# Shuttle.net
KiCad netlist of a schematic drawn in EAGLE
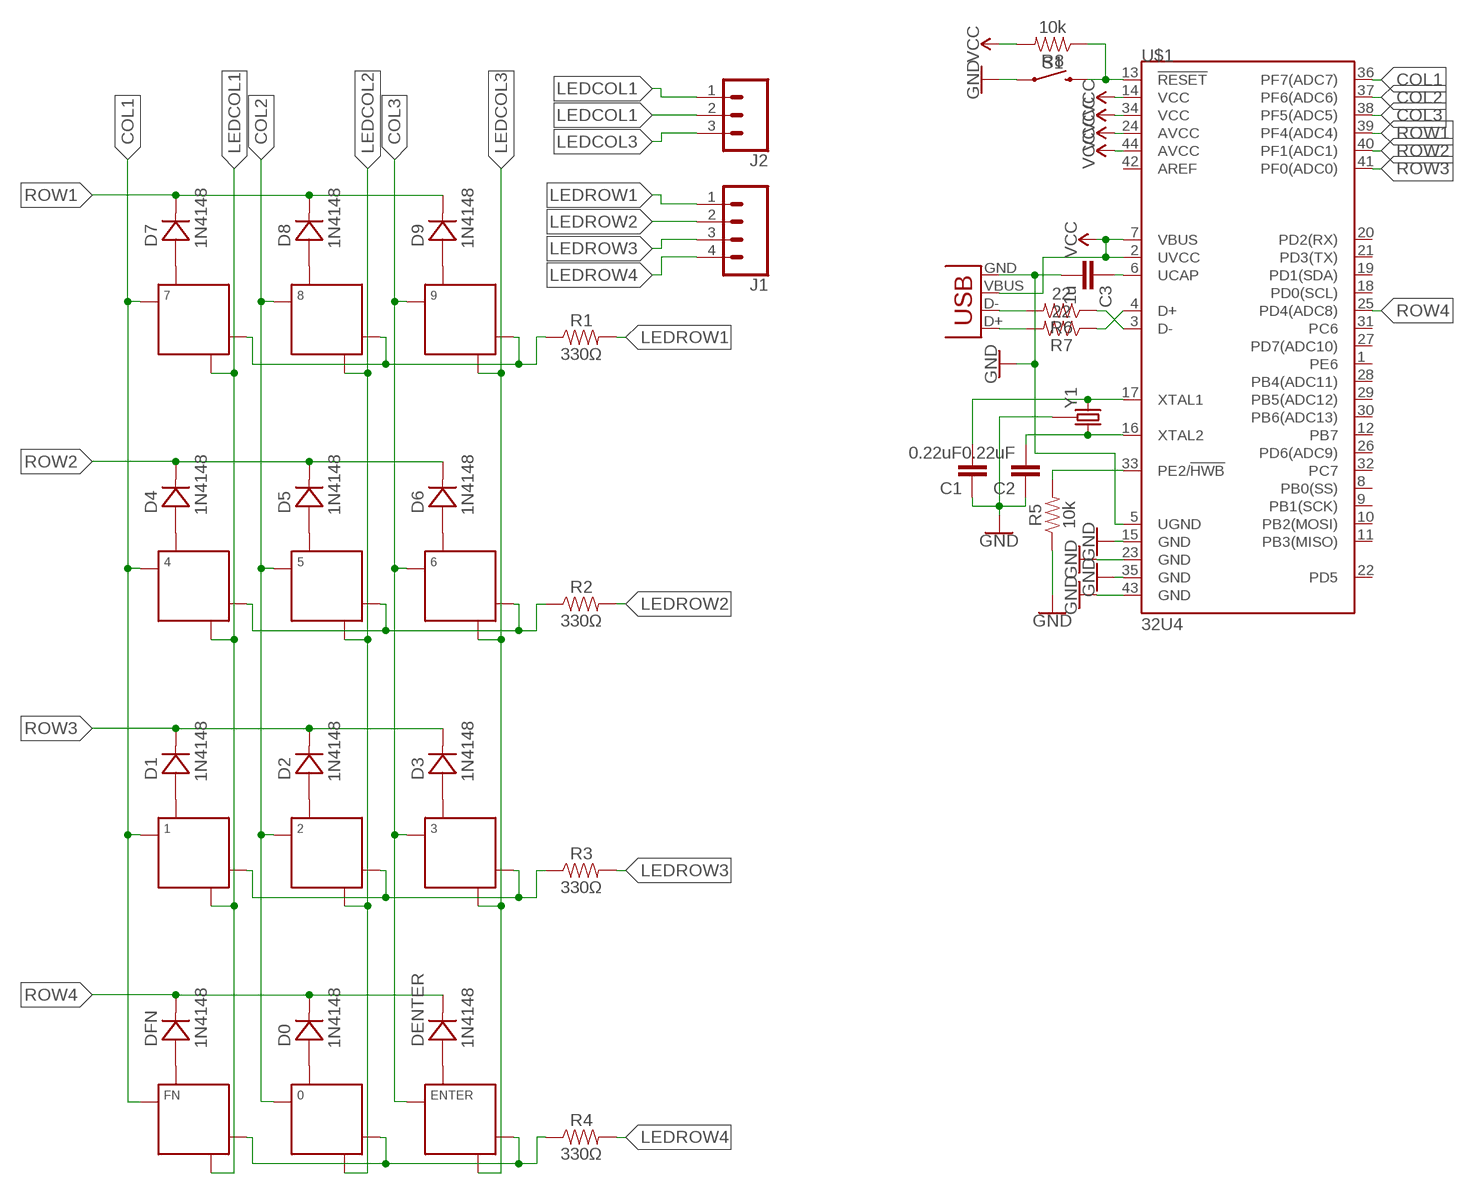
[diagram p0: schematic, sheet 1]

(export (version "E")
  (design (tool "Eeschema 10.0.6"))
  (components
    (comp (ref "0")
      (value "KEYSWITCH-LED-ALPSMX-1U-LED")
      (footprint "eagle-import:ALPSMX-1U-LED")
      (libsource (lib "eagle-import") (part "KEYSWITCH-LED-ALPSMX-1U-LED"))
    )
    (comp (ref "1")
      (value "KEYSWITCH-LED-ALPSMX-1U-LED")
      (footprint "eagle-import:ALPSMX-1U-LED")
      (libsource (lib "eagle-import") (part "KEYSWITCH-LED-ALPSMX-1U-LED"))
    )
    (comp (ref "2")
      (value "KEYSWITCH-LED-ALPSMX-1U-LED")
      (footprint "eagle-import:ALPSMX-1U-LED")
      (libsource (lib "eagle-import") (part "KEYSWITCH-LED-ALPSMX-1U-LED"))
    )
    (comp (ref "3")
      (value "KEYSWITCH-LED-ALPSMX-1U-LED")
      (footprint "eagle-import:ALPSMX-1U-LED")
      (libsource (lib "eagle-import") (part "KEYSWITCH-LED-ALPSMX-1U-LED"))
    )
    (comp (ref "4")
      (value "KEYSWITCH-LED-ALPSMX-1U-LED")
      (footprint "eagle-import:ALPSMX-1U-LED")
      (libsource (lib "eagle-import") (part "KEYSWITCH-LED-ALPSMX-1U-LED"))
    )
    (comp (ref "5")
      (value "KEYSWITCH-LED-ALPSMX-1U-LED")
      (footprint "eagle-import:ALPSMX-1U-LED")
      (libsource (lib "eagle-import") (part "KEYSWITCH-LED-ALPSMX-1U-LED"))
    )
    (comp (ref "6")
      (value "KEYSWITCH-LED-ALPSMX-1U-LED")
      (footprint "eagle-import:ALPSMX-1U-LED")
      (libsource (lib "eagle-import") (part "KEYSWITCH-LED-ALPSMX-1U-LED"))
    )
    (comp (ref "7")
      (value "KEYSWITCH-LED-ALPSMX-1U-LED")
      (footprint "eagle-import:ALPSMX-1U-LED")
      (libsource (lib "eagle-import") (part "KEYSWITCH-LED-ALPSMX-1U-LED"))
    )
    (comp (ref "8")
      (value "KEYSWITCH-LED-ALPSMX-1U-LED")
      (footprint "eagle-import:ALPSMX-1U-LED")
      (libsource (lib "eagle-import") (part "KEYSWITCH-LED-ALPSMX-1U-LED"))
    )
    (comp (ref "9")
      (value "KEYSWITCH-LED-ALPSMX-1U-LED")
      (footprint "eagle-import:ALPSMX-1U-LED")
      (libsource (lib "eagle-import") (part "KEYSWITCH-LED-ALPSMX-1U-LED"))
    )
    (comp (ref "C1")
      (value "0.22uF")
      (footprint "eagle-import:0603")
      (libsource (lib "eagle-import") (part "0.22UF-0603-25V-10%"))
    )
    (comp (ref "C2")
      (value "0.22uF")
      (footprint "eagle-import:0603")
      (libsource (lib "eagle-import") (part "0.22UF-0603-25V-10%"))
    )
    (comp (ref "C3")
      (value "1u")
      (footprint "eagle-import:0603")
      (libsource (lib "eagle-import") (part "0.22UF-0603-25V-10%"))
    )
    (comp (ref "D0")
      (value "1N4148")
      (footprint "eagle-import:DO-35")
      (libsource (lib "eagle-import") (part "DIODE-DO-35"))
    )
    (comp (ref "D1")
      (value "1N4148")
      (footprint "eagle-import:DO-35")
      (libsource (lib "eagle-import") (part "DIODE-DO-35"))
    )
    (comp (ref "D2")
      (value "1N4148")
      (footprint "eagle-import:DO-35")
      (libsource (lib "eagle-import") (part "DIODE-DO-35"))
    )
    (comp (ref "D3")
      (value "1N4148")
      (footprint "eagle-import:DO-35")
      (libsource (lib "eagle-import") (part "DIODE-DO-35"))
    )
    (comp (ref "D4")
      (value "1N4148")
      (footprint "eagle-import:DO-35")
      (libsource (lib "eagle-import") (part "DIODE-DO-35"))
    )
    (comp (ref "D5")
      (value "1N4148")
      (footprint "eagle-import:DO-35")
      (libsource (lib "eagle-import") (part "DIODE-DO-35"))
    )
    (comp (ref "D6")
      (value "1N4148")
      (footprint "eagle-import:DO-35")
      (libsource (lib "eagle-import") (part "DIODE-DO-35"))
    )
    (comp (ref "D7")
      (value "1N4148")
      (footprint "eagle-import:DO-35")
      (libsource (lib "eagle-import") (part "DIODE-DO-35"))
    )
    (comp (ref "D8")
      (value "1N4148")
      (footprint "eagle-import:DO-35")
      (libsource (lib "eagle-import") (part "DIODE-DO-35"))
    )
    (comp (ref "D9")
      (value "1N4148")
      (footprint "eagle-import:DO-35")
      (libsource (lib "eagle-import") (part "DIODE-DO-35"))
    )
    (comp (ref "DENTER")
      (value "1N4148")
      (footprint "eagle-import:DO-35")
      (libsource (lib "eagle-import") (part "DIODE-DO-35"))
    )
    (comp (ref "DFN")
      (value "1N4148")
      (footprint "eagle-import:DO-35")
      (libsource (lib "eagle-import") (part "DIODE-DO-35"))
    )
    (comp (ref "ENTER")
      (value "KEYSWITCH-LED-ALPSMX-1U-LED")
      (footprint "eagle-import:ALPSMX-1U-LED")
      (libsource (lib "eagle-import") (part "KEYSWITCH-LED-ALPSMX-1U-LED"))
    )
    (comp (ref "FN")
      (value "KEYSWITCH-LED-ALPSMX-1U-LED")
      (footprint "eagle-import:ALPSMX-1U-LED")
      (libsource (lib "eagle-import") (part "KEYSWITCH-LED-ALPSMX-1U-LED"))
    )
    (comp (ref "J1")
      (value "CONN_04")
      (footprint "eagle-import:1X04")
      (libsource (lib "eagle-import") (part "CONN_04"))
    )
    (comp (ref "J2")
      (value "CONN_03")
      (footprint "eagle-import:1X03")
      (libsource (lib "eagle-import") (part "CONN_03"))
    )
    (comp (ref "R1")
      (value "330Ω")
      (footprint "eagle-import:AXIAL-0.3")
      (libsource (lib "eagle-import") (part "RESISTORAXIAL-0.3"))
    )
    (comp (ref "R2")
      (value "330Ω")
      (footprint "eagle-import:AXIAL-0.3")
      (libsource (lib "eagle-import") (part "RESISTORAXIAL-0.3"))
    )
    (comp (ref "R3")
      (value "330Ω")
      (footprint "eagle-import:AXIAL-0.3")
      (libsource (lib "eagle-import") (part "RESISTORAXIAL-0.3"))
    )
    (comp (ref "R4")
      (value "330Ω")
      (footprint "eagle-import:AXIAL-0.3")
      (libsource (lib "eagle-import") (part "RESISTORAXIAL-0.3"))
    )
    (comp (ref "R5")
      (value "10k")
      (footprint "eagle-import:AXIAL-0.3")
      (libsource (lib "eagle-import") (part "RESISTORAXIAL-0.3"))
    )
    (comp (ref "R6")
      (value "22")
      (footprint "eagle-import:AXIAL-0.3")
      (libsource (lib "eagle-import") (part "RESISTORAXIAL-0.3"))
    )
    (comp (ref "R7")
      (value "22")
      (footprint "eagle-import:AXIAL-0.3")
      (libsource (lib "eagle-import") (part "RESISTORAXIAL-0.3"))
    )
    (comp (ref "R8")
      (value "10k")
      (footprint "eagle-import:AXIAL-0.3")
      (libsource (lib "eagle-import") (part "RESISTORAXIAL-0.3"))
    )
    (comp (ref "S1")
      (value "MOMENTARY-SWITCH-SPST-PTH-6.0MM")
      (footprint "eagle-import:TACTILE_SWITCH_PTH_6.0MM")
      (libsource (lib "eagle-import") (part "MOMENTARY-SWITCH-SPST-PTH-6.0MM"))
    )
    (comp (ref "U$1")
      (value "32U4")
      (footprint "eagle-import:TQFP44")
      (libsource (lib "eagle-import") (part "ATMEGA32U4TQFP-44"))
    )
    (comp (ref "X1")
      (value "USB-MB-H")
      (footprint "eagle-import:USB-MB-H")
      (libsource (lib "eagle-import") (part "USB-MB-H"))
    )
    (comp (ref "Y1")
      (value "CRYSTAL-GROUNDEDSMD-5X3.2")
      (footprint "eagle-import:CRYSTAL-SMD-5X3.2-4PAD")
      (libsource (lib "eagle-import") (part "CRYSTAL-GROUNDEDSMD-5X3.2"))
    )
  )
  (nets
    (net (code "1") (name "COL1") (class "Default")
      (node (ref "1") (pin "ALPS1") (pinfunction "P0_ALPS1") (pintype "bidirectional"))
      (node (ref "1") (pin "MX1") (pinfunction "P0_MX1") (pintype "bidirectional"))
      (node (ref "4") (pin "ALPS1") (pinfunction "P0_ALPS1") (pintype "bidirectional"))
      (node (ref "4") (pin "MX1") (pinfunction "P0_MX1") (pintype "bidirectional"))
      (node (ref "7") (pin "ALPS1") (pinfunction "P0_ALPS1") (pintype "bidirectional"))
      (node (ref "7") (pin "MX1") (pinfunction "P0_MX1") (pintype "bidirectional"))
      (node (ref "FN") (pin "ALPS1") (pinfunction "P0_ALPS1") (pintype "bidirectional"))
      (node (ref "FN") (pin "MX1") (pinfunction "P0_MX1") (pintype "bidirectional"))
      (node (ref "U$1") (pin "36") (pinfunction "PF7(ADC7)_36") (pintype "bidirectional"))
    )
    (net (code "2") (name "COL2") (class "Default")
      (node (ref "0") (pin "ALPS1") (pinfunction "P0_ALPS1") (pintype "bidirectional"))
      (node (ref "0") (pin "MX1") (pinfunction "P0_MX1") (pintype "bidirectional"))
      (node (ref "2") (pin "ALPS1") (pinfunction "P0_ALPS1") (pintype "bidirectional"))
      (node (ref "2") (pin "MX1") (pinfunction "P0_MX1") (pintype "bidirectional"))
      (node (ref "5") (pin "ALPS1") (pinfunction "P0_ALPS1") (pintype "bidirectional"))
      (node (ref "5") (pin "MX1") (pinfunction "P0_MX1") (pintype "bidirectional"))
      (node (ref "8") (pin "ALPS1") (pinfunction "P0_ALPS1") (pintype "bidirectional"))
      (node (ref "8") (pin "MX1") (pinfunction "P0_MX1") (pintype "bidirectional"))
      (node (ref "U$1") (pin "37") (pinfunction "PF6(ADC6)_37") (pintype "bidirectional"))
    )
    (net (code "3") (name "COL3") (class "Default")
      (node (ref "3") (pin "ALPS1") (pinfunction "P0_ALPS1") (pintype "bidirectional"))
      (node (ref "3") (pin "MX1") (pinfunction "P0_MX1") (pintype "bidirectional"))
      (node (ref "6") (pin "ALPS1") (pinfunction "P0_ALPS1") (pintype "bidirectional"))
      (node (ref "6") (pin "MX1") (pinfunction "P0_MX1") (pintype "bidirectional"))
      (node (ref "9") (pin "ALPS1") (pinfunction "P0_ALPS1") (pintype "bidirectional"))
      (node (ref "9") (pin "MX1") (pinfunction "P0_MX1") (pintype "bidirectional"))
      (node (ref "ENTER") (pin "ALPS1") (pinfunction "P0_ALPS1") (pintype "bidirectional"))
      (node (ref "ENTER") (pin "MX1") (pinfunction "P0_MX1") (pintype "bidirectional"))
      (node (ref "U$1") (pin "38") (pinfunction "PF5(ADC5)_38") (pintype "bidirectional"))
    )
    (net (code "4") (name "GND") (class "Default")
      (node (ref "C1") (pin "1") (pinfunction "1_1") (pintype "passive"))
      (node (ref "C2") (pin "1") (pinfunction "1_1") (pintype "passive"))
      (node (ref "C3") (pin "2") (pinfunction "2_2") (pintype "passive"))
      (node (ref "R5") (pin "P$1") (pinfunction "1_P$1") (pintype "passive"))
      (node (ref "S1") (pin "1") (pinfunction "1_1") (pintype "passive"))
      (node (ref "U$1") (pin "15") (pinfunction "GND_15") (pintype "bidirectional"))
      (node (ref "U$1") (pin "23") (pinfunction "GND_23") (pintype "bidirectional"))
      (node (ref "U$1") (pin "35") (pinfunction "GND_35") (pintype "bidirectional"))
      (node (ref "U$1") (pin "43") (pinfunction "GND_43") (pintype "bidirectional"))
      (node (ref "U$1") (pin "5") (pinfunction "UGND_5") (pintype "bidirectional"))
      (node (ref "X1") (pin "GND") (pinfunction "GND_GND") (pintype "bidirectional"))
      (node (ref "Y1") (pin "2") (pinfunction "3_2") (pintype "passive"))
      (node (ref "Y1") (pin "4") (pinfunction "3_4") (pintype "passive"))
    )
    (net (code "5") (name "LEDCOL1") (class "Default")
      (node (ref "1") (pin "LED+") (pinfunction "LED+_LED+") (pintype "bidirectional"))
      (node (ref "4") (pin "LED+") (pinfunction "LED+_LED+") (pintype "bidirectional"))
      (node (ref "7") (pin "LED+") (pinfunction "LED+_LED+") (pintype "bidirectional"))
      (node (ref "FN") (pin "LED+") (pinfunction "LED+_LED+") (pintype "bidirectional"))
      (node (ref "J2") (pin "1") (pinfunction "1_1") (pintype "passive"))
      (node (ref "J2") (pin "2") (pinfunction "2_2") (pintype "passive"))
    )
    (net (code "6") (name "LEDCOL2") (class "Default")
      (node (ref "0") (pin "LED+") (pinfunction "LED+_LED+") (pintype "bidirectional"))
      (node (ref "2") (pin "LED+") (pinfunction "LED+_LED+") (pintype "bidirectional"))
      (node (ref "5") (pin "LED+") (pinfunction "LED+_LED+") (pintype "bidirectional"))
      (node (ref "8") (pin "LED+") (pinfunction "LED+_LED+") (pintype "bidirectional"))
    )
    (net (code "7") (name "LEDCOL3") (class "Default")
      (node (ref "3") (pin "LED+") (pinfunction "LED+_LED+") (pintype "bidirectional"))
      (node (ref "6") (pin "LED+") (pinfunction "LED+_LED+") (pintype "bidirectional"))
      (node (ref "9") (pin "LED+") (pinfunction "LED+_LED+") (pintype "bidirectional"))
      (node (ref "ENTER") (pin "LED+") (pinfunction "LED+_LED+") (pintype "bidirectional"))
      (node (ref "J2") (pin "3") (pinfunction "3_3") (pintype "passive"))
    )
    (net (code "8") (name "LEDROW1") (class "Default")
      (node (ref "J1") (pin "1") (pinfunction "1_1") (pintype "passive"))
      (node (ref "R1") (pin "P$2") (pinfunction "2_P$2") (pintype "passive"))
    )
    (net (code "9") (name "LEDROW2") (class "Default")
      (node (ref "J1") (pin "2") (pinfunction "2_2") (pintype "passive"))
      (node (ref "R2") (pin "P$2") (pinfunction "2_P$2") (pintype "passive"))
    )
    (net (code "10") (name "LEDROW3") (class "Default")
      (node (ref "J1") (pin "3") (pinfunction "3_3") (pintype "passive"))
      (node (ref "R3") (pin "P$2") (pinfunction "2_P$2") (pintype "passive"))
    )
    (net (code "11") (name "LEDROW4") (class "Default")
      (node (ref "J1") (pin "4") (pinfunction "4_4") (pintype "passive"))
      (node (ref "R4") (pin "P$2") (pinfunction "2_P$2") (pintype "passive"))
    )
    (net (code "12") (name "Net-(0-P1-PadALPS2)") (class "Default")
      (node (ref "0") (pin "ALPS2") (pinfunction "P1_ALPS2") (pintype "bidirectional"))
      (node (ref "0") (pin "MX2") (pinfunction "P1_MX2") (pintype "bidirectional"))
      (node (ref "D0") (pin "A") (pinfunction "A_A") (pintype "passive"))
    )
    (net (code "13") (name "Net-(1-P1-PadALPS2)") (class "Default")
      (node (ref "1") (pin "ALPS2") (pinfunction "P1_ALPS2") (pintype "bidirectional"))
      (node (ref "1") (pin "MX2") (pinfunction "P1_MX2") (pintype "bidirectional"))
      (node (ref "D1") (pin "A") (pinfunction "A_A") (pintype "passive"))
    )
    (net (code "14") (name "Net-(2-P1-PadALPS2)") (class "Default")
      (node (ref "2") (pin "ALPS2") (pinfunction "P1_ALPS2") (pintype "bidirectional"))
      (node (ref "2") (pin "MX2") (pinfunction "P1_MX2") (pintype "bidirectional"))
      (node (ref "D2") (pin "A") (pinfunction "A_A") (pintype "passive"))
    )
    (net (code "15") (name "Net-(3-P1-PadALPS2)") (class "Default")
      (node (ref "3") (pin "ALPS2") (pinfunction "P1_ALPS2") (pintype "bidirectional"))
      (node (ref "3") (pin "MX2") (pinfunction "P1_MX2") (pintype "bidirectional"))
      (node (ref "D3") (pin "A") (pinfunction "A_A") (pintype "passive"))
    )
    (net (code "16") (name "Net-(4-P1-PadALPS2)") (class "Default")
      (node (ref "4") (pin "ALPS2") (pinfunction "P1_ALPS2") (pintype "bidirectional"))
      (node (ref "4") (pin "MX2") (pinfunction "P1_MX2") (pintype "bidirectional"))
      (node (ref "D4") (pin "A") (pinfunction "A_A") (pintype "passive"))
    )
    (net (code "17") (name "Net-(5-P1-PadALPS2)") (class "Default")
      (node (ref "5") (pin "ALPS2") (pinfunction "P1_ALPS2") (pintype "bidirectional"))
      (node (ref "5") (pin "MX2") (pinfunction "P1_MX2") (pintype "bidirectional"))
      (node (ref "D5") (pin "A") (pinfunction "A_A") (pintype "passive"))
    )
    (net (code "18") (name "Net-(6-P1-PadALPS2)") (class "Default")
      (node (ref "6") (pin "ALPS2") (pinfunction "P1_ALPS2") (pintype "bidirectional"))
      (node (ref "6") (pin "MX2") (pinfunction "P1_MX2") (pintype "bidirectional"))
      (node (ref "D6") (pin "A") (pinfunction "A_A") (pintype "passive"))
    )
    (net (code "19") (name "Net-(7-P1-PadALPS2)") (class "Default")
      (node (ref "7") (pin "ALPS2") (pinfunction "P1_ALPS2") (pintype "bidirectional"))
      (node (ref "7") (pin "MX2") (pinfunction "P1_MX2") (pintype "bidirectional"))
      (node (ref "D7") (pin "A") (pinfunction "A_A") (pintype "passive"))
    )
    (net (code "20") (name "Net-(8-P1-PadALPS2)") (class "Default")
      (node (ref "8") (pin "ALPS2") (pinfunction "P1_ALPS2") (pintype "bidirectional"))
      (node (ref "8") (pin "MX2") (pinfunction "P1_MX2") (pintype "bidirectional"))
      (node (ref "D8") (pin "A") (pinfunction "A_A") (pintype "passive"))
    )
    (net (code "21") (name "Net-(9-P1-PadALPS2)") (class "Default")
      (node (ref "9") (pin "ALPS2") (pinfunction "P1_ALPS2") (pintype "bidirectional"))
      (node (ref "9") (pin "MX2") (pinfunction "P1_MX2") (pintype "bidirectional"))
      (node (ref "D9") (pin "A") (pinfunction "A_A") (pintype "passive"))
    )
    (net (code "22") (name "Net-(DENTER-PadA)") (class "Default")
      (node (ref "DENTER") (pin "A") (pinfunction "A_A") (pintype "passive"))
      (node (ref "ENTER") (pin "ALPS2") (pinfunction "P1_ALPS2") (pintype "bidirectional"))
      (node (ref "ENTER") (pin "MX2") (pinfunction "P1_MX2") (pintype "bidirectional"))
    )
    (net (code "23") (name "Net-(DFN-PadA)") (class "Default")
      (node (ref "DFN") (pin "A") (pinfunction "A_A") (pintype "passive"))
      (node (ref "FN") (pin "ALPS2") (pinfunction "P1_ALPS2") (pintype "bidirectional"))
      (node (ref "FN") (pin "MX2") (pinfunction "P1_MX2") (pintype "bidirectional"))
    )
    (net (code "24") (name "Net-(R1-1)") (class "Default")
      (node (ref "7") (pin "LED-") (pinfunction "LED-_LED-") (pintype "bidirectional"))
      (node (ref "8") (pin "LED-") (pinfunction "LED-_LED-") (pintype "bidirectional"))
      (node (ref "9") (pin "LED-") (pinfunction "LED-_LED-") (pintype "bidirectional"))
      (node (ref "R1") (pin "P$1") (pinfunction "1_P$1") (pintype "passive"))
    )
    (net (code "25") (name "Net-(R2-1)") (class "Default")
      (node (ref "4") (pin "LED-") (pinfunction "LED-_LED-") (pintype "bidirectional"))
      (node (ref "5") (pin "LED-") (pinfunction "LED-_LED-") (pintype "bidirectional"))
      (node (ref "6") (pin "LED-") (pinfunction "LED-_LED-") (pintype "bidirectional"))
      (node (ref "R2") (pin "P$1") (pinfunction "1_P$1") (pintype "passive"))
    )
    (net (code "26") (name "Net-(R3-1)") (class "Default")
      (node (ref "1") (pin "LED-") (pinfunction "LED-_LED-") (pintype "bidirectional"))
      (node (ref "2") (pin "LED-") (pinfunction "LED-_LED-") (pintype "bidirectional"))
      (node (ref "3") (pin "LED-") (pinfunction "LED-_LED-") (pintype "bidirectional"))
      (node (ref "R3") (pin "P$1") (pinfunction "1_P$1") (pintype "passive"))
    )
    (net (code "27") (name "Net-(R4-1)") (class "Default")
      (node (ref "0") (pin "LED-") (pinfunction "LED-_LED-") (pintype "bidirectional"))
      (node (ref "ENTER") (pin "LED-") (pinfunction "LED-_LED-") (pintype "bidirectional"))
      (node (ref "FN") (pin "LED-") (pinfunction "LED-_LED-") (pintype "bidirectional"))
      (node (ref "R4") (pin "P$1") (pinfunction "1_P$1") (pintype "passive"))
    )
    (net (code "28") (name "Net-(R5-2)") (class "Default")
      (node (ref "R5") (pin "P$2") (pinfunction "2_P$2") (pintype "passive"))
      (node (ref "U$1") (pin "33") (pinfunction "PE2/~{HWB}_33") (pintype "bidirectional"))
    )
    (net (code "29") (name "Net-(R6-1)") (class "Default")
      (node (ref "R6") (pin "P$1") (pinfunction "1_P$1") (pintype "passive"))
      (node (ref "U$1") (pin "3") (pinfunction "D-_3") (pintype "bidirectional"))
    )
    (net (code "30") (name "Net-(R6-2)") (class "Default")
      (node (ref "R6") (pin "P$2") (pinfunction "2_P$2") (pintype "passive"))
      (node (ref "X1") (pin "D-") (pinfunction "D-_D-") (pintype "bidirectional"))
    )
    (net (code "31") (name "Net-(R7-1)") (class "Default")
      (node (ref "R7") (pin "P$1") (pinfunction "1_P$1") (pintype "passive"))
      (node (ref "U$1") (pin "4") (pinfunction "D+_4") (pintype "bidirectional"))
    )
    (net (code "32") (name "Net-(R7-2)") (class "Default")
      (node (ref "R7") (pin "P$2") (pinfunction "2_P$2") (pintype "passive"))
      (node (ref "X1") (pin "D+") (pinfunction "D+_D+") (pintype "bidirectional"))
    )
    (net (code "33") (name "Net-(R8-1)") (class "Default")
      (node (ref "R8") (pin "P$1") (pinfunction "1_P$1") (pintype "passive"))
      (node (ref "S1") (pin "3") (pinfunction "2_3") (pintype "passive"))
      (node (ref "U$1") (pin "13") (pinfunction "~{RESET}_13") (pintype "bidirectional"))
    )
    (net (code "34") (name "Net-(U$1-UCAP)") (class "Default")
      (node (ref "C3") (pin "1") (pinfunction "1_1") (pintype "passive"))
      (node (ref "U$1") (pin "6") (pinfunction "UCAP_6") (pintype "bidirectional"))
    )
    (net (code "35") (name "Net-(U$1-XTAL1)") (class "Default")
      (node (ref "C1") (pin "2") (pinfunction "2_2") (pintype "passive"))
      (node (ref "U$1") (pin "17") (pinfunction "XTAL1_17") (pintype "bidirectional"))
      (node (ref "Y1") (pin "3") (pinfunction "1_3") (pintype "passive"))
    )
    (net (code "36") (name "Net-(U$1-XTAL2)") (class "Default")
      (node (ref "C2") (pin "2") (pinfunction "2_2") (pintype "passive"))
      (node (ref "U$1") (pin "16") (pinfunction "XTAL2_16") (pintype "bidirectional"))
      (node (ref "Y1") (pin "1") (pinfunction "2_1") (pintype "passive"))
    )
    (net (code "37") (name "ROW1") (class "Default")
      (node (ref "D7") (pin "C") (pinfunction "C_C") (pintype "passive"))
      (node (ref "D8") (pin "C") (pinfunction "C_C") (pintype "passive"))
      (node (ref "D9") (pin "C") (pinfunction "C_C") (pintype "passive"))
      (node (ref "U$1") (pin "39") (pinfunction "PF4(ADC4)_39") (pintype "bidirectional"))
    )
    (net (code "38") (name "ROW2") (class "Default")
      (node (ref "D4") (pin "C") (pinfunction "C_C") (pintype "passive"))
      (node (ref "D5") (pin "C") (pinfunction "C_C") (pintype "passive"))
      (node (ref "D6") (pin "C") (pinfunction "C_C") (pintype "passive"))
      (node (ref "U$1") (pin "40") (pinfunction "PF1(ADC1)_40") (pintype "bidirectional"))
    )
    (net (code "39") (name "ROW3") (class "Default")
      (node (ref "D1") (pin "C") (pinfunction "C_C") (pintype "passive"))
      (node (ref "D2") (pin "C") (pinfunction "C_C") (pintype "passive"))
      (node (ref "D3") (pin "C") (pinfunction "C_C") (pintype "passive"))
      (node (ref "U$1") (pin "41") (pinfunction "PF0(ADC0)_41") (pintype "bidirectional"))
    )
    (net (code "40") (name "ROW4") (class "Default")
      (node (ref "D0") (pin "C") (pinfunction "C_C") (pintype "passive"))
      (node (ref "DENTER") (pin "C") (pinfunction "C_C") (pintype "passive"))
      (node (ref "DFN") (pin "C") (pinfunction "C_C") (pintype "passive"))
      (node (ref "U$1") (pin "25") (pinfunction "PD4(ADC8)_25") (pintype "bidirectional"))
    )
    (net (code "41") (name "VCC") (class "Default")
      (node (ref "R8") (pin "P$2") (pinfunction "2_P$2") (pintype "passive"))
      (node (ref "U$1") (pin "14") (pinfunction "VCC_14") (pintype "bidirectional"))
      (node (ref "U$1") (pin "2") (pinfunction "UVCC_2") (pintype "bidirectional"))
      (node (ref "U$1") (pin "24") (pinfunction "AVCC_24") (pintype "bidirectional"))
      (node (ref "U$1") (pin "34") (pinfunction "VCC_34") (pintype "bidirectional"))
      (node (ref "U$1") (pin "44") (pinfunction "AVCC_44") (pintype "bidirectional"))
      (node (ref "U$1") (pin "7") (pinfunction "VBUS_7") (pintype "bidirectional"))
      (node (ref "X1") (pin "VBUS") (pinfunction "VBUS_VBUS") (pintype "bidirectional"))
    )
    (net (code "42") (name "unconnected-(U$1-AREF-Pad42)") (class "Default")
      (node (ref "U$1") (pin "42") (pinfunction "AREF_42") (pintype "bidirectional"))
    )
    (net (code "43") (name "unconnected-(U$1-PB0(SS)-Pad8)") (class "Default")
      (node (ref "U$1") (pin "8") (pinfunction "PB0(SS)_8") (pintype "bidirectional"))
    )
    (net (code "44") (name "unconnected-(U$1-PB1(SCK)-Pad9)") (class "Default")
      (node (ref "U$1") (pin "9") (pinfunction "PB1(SCK)_9") (pintype "bidirectional"))
    )
    (net (code "45") (name "unconnected-(U$1-PB2(MOSI)-Pad10)") (class "Default")
      (node (ref "U$1") (pin "10") (pinfunction "PB2(MOSI)_10") (pintype "bidirectional"))
    )
    (net (code "46") (name "unconnected-(U$1-PB3(MISO)-Pad11)") (class "Default")
      (node (ref "U$1") (pin "11") (pinfunction "PB3(MISO)_11") (pintype "bidirectional"))
    )
    (net (code "47") (name "unconnected-(U$1-PB4(ADC11)-Pad28)") (class "Default")
      (node (ref "U$1") (pin "28") (pinfunction "PB4(ADC11)_28") (pintype "bidirectional"))
    )
    (net (code "48") (name "unconnected-(U$1-PB5(ADC12)-Pad29)") (class "Default")
      (node (ref "U$1") (pin "29") (pinfunction "PB5(ADC12)_29") (pintype "bidirectional"))
    )
    (net (code "49") (name "unconnected-(U$1-PB6(ADC13)-Pad30)") (class "Default")
      (node (ref "U$1") (pin "30") (pinfunction "PB6(ADC13)_30") (pintype "bidirectional"))
    )
    (net (code "50") (name "unconnected-(U$1-PB7-Pad12)") (class "Default")
      (node (ref "U$1") (pin "12") (pinfunction "PB7_12") (pintype "bidirectional"))
    )
    (net (code "51") (name "unconnected-(U$1-PC6-Pad31)") (class "Default")
      (node (ref "U$1") (pin "31") (pinfunction "PC6_31") (pintype "bidirectional"))
    )
    (net (code "52") (name "unconnected-(U$1-PC7-Pad32)") (class "Default")
      (node (ref "U$1") (pin "32") (pinfunction "PC7_32") (pintype "bidirectional"))
    )
    (net (code "53") (name "unconnected-(U$1-PD0(SCL)-Pad18)") (class "Default")
      (node (ref "U$1") (pin "18") (pinfunction "PD0(SCL)_18") (pintype "bidirectional"))
    )
    (net (code "54") (name "unconnected-(U$1-PD1(SDA)-Pad19)") (class "Default")
      (node (ref "U$1") (pin "19") (pinfunction "PD1(SDA)_19") (pintype "bidirectional"))
    )
    (net (code "55") (name "unconnected-(U$1-PD2(RX)-Pad20)") (class "Default")
      (node (ref "U$1") (pin "20") (pinfunction "PD2(RX)_20") (pintype "bidirectional"))
    )
    (net (code "56") (name "unconnected-(U$1-PD3(TX)-Pad21)") (class "Default")
      (node (ref "U$1") (pin "21") (pinfunction "PD3(TX)_21") (pintype "bidirectional"))
    )
    (net (code "57") (name "unconnected-(U$1-PD5-Pad22)") (class "Default")
      (node (ref "U$1") (pin "22") (pinfunction "PD5_22") (pintype "bidirectional"))
    )
    (net (code "58") (name "unconnected-(U$1-PD6(ADC9)-Pad26)") (class "Default")
      (node (ref "U$1") (pin "26") (pinfunction "PD6(ADC9)_26") (pintype "bidirectional"))
    )
    (net (code "59") (name "unconnected-(U$1-PD7(ADC10)-Pad27)") (class "Default")
      (node (ref "U$1") (pin "27") (pinfunction "PD7(ADC10)_27") (pintype "bidirectional"))
    )
    (net (code "60") (name "unconnected-(U$1-PE6-Pad1)") (class "Default")
      (node (ref "U$1") (pin "1") (pinfunction "PE6_1") (pintype "bidirectional"))
    )
  )
)
